# Board.net
KiCad netlist of a schematic drawn in Altium Designer
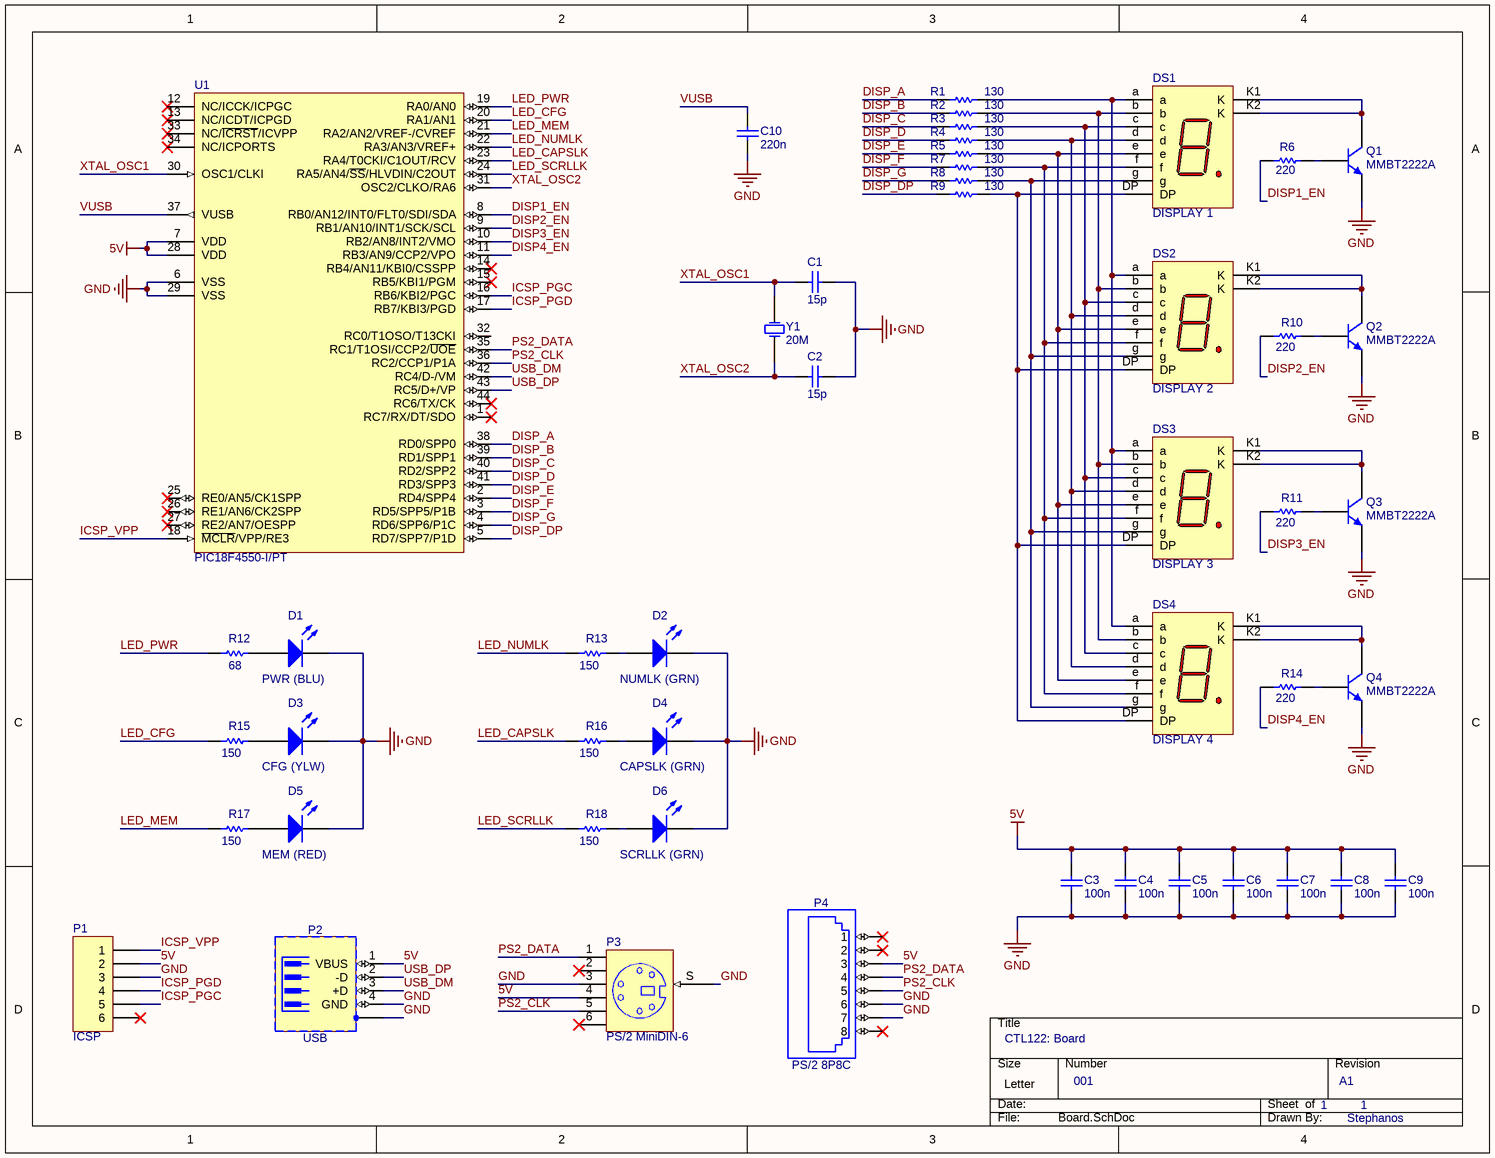
[diagram p0: Board.SchDoc]

(export (version "E")
  (design (tool "Eeschema 10.0.6"))
  (components
    (comp (ref "C1")
      (value "15p")
      (footprint "0805")
      (description "Capacitor")
      (fields (field (name "Comment") "CAP"))
      (libsource (lib "XNSFundamental") (part "CAP"))
    )
    (comp (ref "C2")
      (value "15p")
      (footprint "0805")
      (description "Capacitor")
      (fields (field (name "Comment") "CAP"))
      (libsource (lib "XNSFundamental") (part "CAP"))
    )
    (comp (ref "C3")
      (value "100n")
      (footprint "0805")
      (description "Capacitor")
      (fields (field (name "Comment") "CAP"))
      (libsource (lib "XNSFundamental") (part "CAP"))
    )
    (comp (ref "C4")
      (value "100n")
      (footprint "0805")
      (description "Capacitor")
      (fields (field (name "Comment") "CAP"))
      (libsource (lib "XNSFundamental") (part "CAP"))
    )
    (comp (ref "C5")
      (value "100n")
      (footprint "0805")
      (description "Capacitor")
      (fields (field (name "Comment") "CAP"))
      (libsource (lib "XNSFundamental") (part "CAP"))
    )
    (comp (ref "C6")
      (value "100n")
      (footprint "0805")
      (description "Capacitor")
      (fields (field (name "Comment") "CAP"))
      (libsource (lib "XNSFundamental") (part "CAP"))
    )
    (comp (ref "C7")
      (value "100n")
      (footprint "0805")
      (description "Capacitor")
      (fields (field (name "Comment") "CAP"))
      (libsource (lib "XNSFundamental") (part "CAP"))
    )
    (comp (ref "C8")
      (value "100n")
      (footprint "0805")
      (description "Capacitor")
      (fields (field (name "Comment") "CAP"))
      (libsource (lib "XNSFundamental") (part "CAP"))
    )
    (comp (ref "C9")
      (value "100n")
      (footprint "0805")
      (description "Capacitor")
      (fields (field (name "Comment") "CAP"))
      (libsource (lib "XNSFundamental") (part "CAP"))
    )
    (comp (ref "C10")
      (value "220n")
      (footprint "0805")
      (description "Capacitor")
      (fields (field (name "Comment") "CAP"))
      (libsource (lib "XNSFundamental") (part "CAP"))
    )
    (comp (ref "D1")
      (value "PWR (BLU)")
      (footprint "1206P")
      (description "Light Emitting Diode")
      (libsource (lib "XNSSemiconductor") (part "LED"))
    )
    (comp (ref "D2")
      (value "NUMLK (GRN)")
      (footprint "1206P")
      (description "Light Emitting Diode")
      (libsource (lib "XNSSemiconductor") (part "LED"))
    )
    (comp (ref "D3")
      (value "CFG (YLW)")
      (footprint "1206P")
      (description "Light Emitting Diode")
      (libsource (lib "XNSSemiconductor") (part "LED"))
    )
    (comp (ref "D4")
      (value "CAPSLK (GRN)")
      (footprint "1206P")
      (description "Light Emitting Diode")
      (libsource (lib "XNSSemiconductor") (part "LED"))
    )
    (comp (ref "D5")
      (value "MEM (RED)")
      (footprint "1206P")
      (description "Light Emitting Diode")
      (libsource (lib "XNSSemiconductor") (part "LED"))
    )
    (comp (ref "D6")
      (value "SCRLLK (GRN)")
      (footprint "1206P")
      (description "Light Emitting Diode")
      (libsource (lib "XNSSemiconductor") (part "LED"))
    )
    (comp (ref "DS1")
      (value "DISPLAY 1")
      (footprint "7SEG")
      (description "7-segment Display Common Cathode")
      (libsource (lib "XNSModule") (part "7SEG-CC"))
    )
    (comp (ref "DS2")
      (value "DISPLAY 2")
      (footprint "7SEG")
      (description "7-segment Display Common Cathode")
      (libsource (lib "XNSModule") (part "7SEG-CC"))
    )
    (comp (ref "DS3")
      (value "DISPLAY 3")
      (footprint "7SEG")
      (description "7-segment Display Common Cathode")
      (libsource (lib "XNSModule") (part "7SEG-CC"))
    )
    (comp (ref "DS4")
      (value "DISPLAY 4")
      (footprint "7SEG")
      (description "7-segment Display Common Cathode")
      (libsource (lib "XNSModule") (part "7SEG-CC"))
    )
    (comp (ref "P1")
      (value "ICSP")
      (footprint "HDR1X6")
      (description "Header, 6-Pin")
      (fields (field (name "PUBLISHER") "Altium Limited"))
      (libsource (lib "Miscellaneous Connectors") (part "Header 6"))
    )
    (comp (ref "P2")
      (value "USB")
      (footprint "TYCO_292304-1")
      (description "4 Pin + 1 Shield USB Receptacle")
      (fields
        (field (name "PART NUMBER") "TYCO_292304-1")
        (field (name "MANUFACTURER") "TYCO ELECTRONICS")
        (field (name "AUTHOR") "CERN DEM JLC")
      )
      (libsource (lib "Connectors") (part "Connector USB 4 Pin + 1Shield"))
    )
    (comp (ref "P3")
      (value "PS/2 MiniDIN-6")
      (footprint "PS2-6PIN")
      (description "6 Pin Through Hole PS2 Socket (Kycon P/N)")
      (fields (field (name "PUBLISHER") "Altium Limited"))
      (libsource (lib "Miscellaneous Connectors") (part "PS2-6PIN"))
    )
    (comp (ref "P4")
      (value "PS/2 8P8C")
      (footprint "FCI_54602-908LF")
      (description "1 Port, 8 Positions, CAT3 RJ45 Horizontal Modular Jack")
      (fields
        (field (name "PART NUMBER") "FCI_54602-908LF")
        (field (name "MANUFACTURER") "FCI")
        (field (name "AUTHOR") "CERN DEM JLC")
      )
      (libsource (lib "Connectors") (part "FCI_54602-908LF"))
    )
    (comp (ref "Q1")
      (value "MMBT2222A")
      (footprint "SOT-23")
      (description "Bipolar NPN Transistor")
      (libsource (lib "XNSSemiconductor") (part "NPN"))
    )
    (comp (ref "Q2")
      (value "MMBT2222A")
      (footprint "SOT-23")
      (description "Bipolar NPN Transistor")
      (libsource (lib "XNSSemiconductor") (part "NPN"))
    )
    (comp (ref "Q3")
      (value "MMBT2222A")
      (footprint "SOT-23")
      (description "Bipolar NPN Transistor")
      (libsource (lib "XNSSemiconductor") (part "NPN"))
    )
    (comp (ref "Q4")
      (value "MMBT2222A")
      (footprint "SOT-23")
      (description "Bipolar NPN Transistor")
      (libsource (lib "XNSSemiconductor") (part "NPN"))
    )
    (comp (ref "R1")
      (value "130")
      (footprint "0805")
      (description "Resistor")
      (fields (field (name "Comment") "RES"))
      (libsource (lib "XNSFundamental") (part "RES"))
    )
    (comp (ref "R2")
      (value "130")
      (footprint "0805")
      (description "Resistor")
      (fields (field (name "Comment") "RES"))
      (libsource (lib "XNSFundamental") (part "RES"))
    )
    (comp (ref "R3")
      (value "130")
      (footprint "0805")
      (description "Resistor")
      (fields (field (name "Comment") "RES"))
      (libsource (lib "XNSFundamental") (part "RES"))
    )
    (comp (ref "R4")
      (value "130")
      (footprint "0805")
      (description "Resistor")
      (fields (field (name "Comment") "RES"))
      (libsource (lib "XNSFundamental") (part "RES"))
    )
    (comp (ref "R5")
      (value "130")
      (footprint "0805")
      (description "Resistor")
      (fields (field (name "Comment") "RES"))
      (libsource (lib "XNSFundamental") (part "RES"))
    )
    (comp (ref "R6")
      (value "220")
      (footprint "0805")
      (description "Resistor")
      (fields (field (name "Comment") "RES"))
      (libsource (lib "XNSFundamental") (part "RES"))
    )
    (comp (ref "R7")
      (value "130")
      (footprint "0805")
      (description "Resistor")
      (fields (field (name "Comment") "RES"))
      (libsource (lib "XNSFundamental") (part "RES"))
    )
    (comp (ref "R8")
      (value "130")
      (footprint "0805")
      (description "Resistor")
      (fields (field (name "Comment") "RES"))
      (libsource (lib "XNSFundamental") (part "RES"))
    )
    (comp (ref "R9")
      (value "130")
      (footprint "0805")
      (description "Resistor")
      (fields (field (name "Comment") "RES"))
      (libsource (lib "XNSFundamental") (part "RES"))
    )
    (comp (ref "R10")
      (value "220")
      (footprint "0805")
      (description "Resistor")
      (fields (field (name "Comment") "RES"))
      (libsource (lib "XNSFundamental") (part "RES"))
    )
    (comp (ref "R11")
      (value "220")
      (footprint "0805")
      (description "Resistor")
      (fields (field (name "Comment") "RES"))
      (libsource (lib "XNSFundamental") (part "RES"))
    )
    (comp (ref "R12")
      (value "68")
      (footprint "0805")
      (description "Resistor")
      (fields (field (name "Comment") "RES"))
      (libsource (lib "XNSFundamental") (part "RES"))
    )
    (comp (ref "R13")
      (value "150")
      (footprint "0805")
      (description "Resistor")
      (fields (field (name "Comment") "RES"))
      (libsource (lib "XNSFundamental") (part "RES"))
    )
    (comp (ref "R14")
      (value "220")
      (footprint "0805")
      (description "Resistor")
      (fields (field (name "Comment") "RES"))
      (libsource (lib "XNSFundamental") (part "RES"))
    )
    (comp (ref "R15")
      (value "150")
      (footprint "0805")
      (description "Resistor")
      (fields (field (name "Comment") "RES"))
      (libsource (lib "XNSFundamental") (part "RES"))
    )
    (comp (ref "R16")
      (value "150")
      (footprint "0805")
      (description "Resistor")
      (fields (field (name "Comment") "RES"))
      (libsource (lib "XNSFundamental") (part "RES"))
    )
    (comp (ref "R17")
      (value "150")
      (footprint "0805")
      (description "Resistor")
      (fields (field (name "Comment") "RES"))
      (libsource (lib "XNSFundamental") (part "RES"))
    )
    (comp (ref "R18")
      (value "150")
      (footprint "0805")
      (description "Resistor")
      (fields (field (name "Comment") "RES"))
      (libsource (lib "XNSFundamental") (part "RES"))
    )
    (comp (ref "U1")
      (value "PIC18F4550-I/PT")
      (footprint "TQFP-PT44_N")
      (fields (field (name "PUBLISHER") "Altium Limited"))
      (libsource (lib "Microchip Microcontroller 8-Bit PIC18") (part "PIC18F4550-I/PT"))
    )
    (comp (ref "Y1")
      (value "20M")
      (footprint "HC49")
      (description "Crystal Oscillator")
      (fields (field (name "Comment") "XTAL"))
      (libsource (lib "XNSFundamental") (part "XTAL"))
    )
  )
  (nets
    (net (code "1") (name "/DISP1_EN") (class "Default")
      (node (ref "R6") (pin "1") (pinfunction "1_1") (pintype "passive"))
      (node (ref "U1") (pin "8") (pinfunction "RB0/AN12/INT0/FLT0/SDI/SDA_8") (pintype "bidirectional"))
    )
    (net (code "2") (name "/DISP2_EN") (class "Default")
      (node (ref "R10") (pin "1") (pinfunction "1_1") (pintype "passive"))
      (node (ref "U1") (pin "9") (pinfunction "RB1/AN10/INT1/SCK/SCL_9") (pintype "bidirectional"))
    )
    (net (code "3") (name "/DISP3_EN") (class "Default")
      (node (ref "R11") (pin "1") (pinfunction "1_1") (pintype "passive"))
      (node (ref "U1") (pin "10") (pinfunction "RB2/AN8/INT2/VMO_10") (pintype "bidirectional"))
    )
    (net (code "4") (name "/DISP4_EN") (class "Default")
      (node (ref "R14") (pin "1") (pinfunction "1_1") (pintype "passive"))
      (node (ref "U1") (pin "11") (pinfunction "RB3/AN9/CCP2/VPO_11") (pintype "bidirectional"))
    )
    (net (code "5") (name "/DISP_A") (class "Default")
      (node (ref "R1") (pin "1") (pinfunction "1_1") (pintype "passive"))
      (node (ref "U1") (pin "38") (pinfunction "RD0/SPP0_38") (pintype "bidirectional"))
    )
    (net (code "6") (name "/DISP_B") (class "Default")
      (node (ref "R2") (pin "1") (pinfunction "1_1") (pintype "passive"))
      (node (ref "U1") (pin "39") (pinfunction "RD1/SPP1_39") (pintype "bidirectional"))
    )
    (net (code "7") (name "/DISP_C") (class "Default")
      (node (ref "R3") (pin "1") (pinfunction "1_1") (pintype "passive"))
      (node (ref "U1") (pin "40") (pinfunction "RD2/SPP2_40") (pintype "bidirectional"))
    )
    (net (code "8") (name "/DISP_D") (class "Default")
      (node (ref "R4") (pin "1") (pinfunction "1_1") (pintype "passive"))
      (node (ref "U1") (pin "41") (pinfunction "RD3/SPP3_41") (pintype "bidirectional"))
    )
    (net (code "9") (name "/DISP_DP") (class "Default")
      (node (ref "R9") (pin "1") (pinfunction "1_1") (pintype "passive"))
      (node (ref "U1") (pin "5") (pinfunction "RD7/SPP7/P1D_5") (pintype "bidirectional"))
    )
    (net (code "10") (name "/DISP_E") (class "Default")
      (node (ref "R5") (pin "1") (pinfunction "1_1") (pintype "passive"))
      (node (ref "U1") (pin "2") (pinfunction "RD4/SPP4_2") (pintype "bidirectional"))
    )
    (net (code "11") (name "/DISP_F") (class "Default")
      (node (ref "R7") (pin "1") (pinfunction "1_1") (pintype "passive"))
      (node (ref "U1") (pin "3") (pinfunction "RD5/SPP5/P1B_3") (pintype "bidirectional"))
    )
    (net (code "12") (name "/DISP_G") (class "Default")
      (node (ref "R8") (pin "1") (pinfunction "1_1") (pintype "passive"))
      (node (ref "U1") (pin "4") (pinfunction "RD6/SPP6/P1C_4") (pintype "bidirectional"))
    )
    (net (code "13") (name "/ICSP_PGC") (class "Default")
      (node (ref "P1") (pin "5") (pinfunction "5_5") (pintype "passive"))
      (node (ref "U1") (pin "16") (pinfunction "RB6/KBI2/PGC_16") (pintype "bidirectional"))
    )
    (net (code "14") (name "/ICSP_PGD") (class "Default")
      (node (ref "P1") (pin "4") (pinfunction "4_4") (pintype "passive"))
      (node (ref "U1") (pin "17") (pinfunction "RB7/KBI3/PGD_17") (pintype "bidirectional"))
    )
    (net (code "15") (name "/ICSP_VPP") (class "Default")
      (node (ref "P1") (pin "1") (pinfunction "1_1") (pintype "passive"))
      (node (ref "U1") (pin "18") (pinfunction "~{MCLR}/VPP/RE3_18") (pintype "input"))
    )
    (net (code "16") (name "/LED_CAPSLK") (class "Default")
      (node (ref "R16") (pin "1") (pinfunction "1_1") (pintype "passive"))
      (node (ref "U1") (pin "23") (pinfunction "RA4/T0CKI/C1OUT/RCV_23") (pintype "bidirectional"))
    )
    (net (code "17") (name "/LED_CFG") (class "Default")
      (node (ref "R15") (pin "1") (pinfunction "1_1") (pintype "passive"))
      (node (ref "U1") (pin "20") (pinfunction "RA1/AN1_20") (pintype "bidirectional"))
    )
    (net (code "18") (name "/LED_MEM") (class "Default")
      (node (ref "R17") (pin "1") (pinfunction "1_1") (pintype "passive"))
      (node (ref "U1") (pin "21") (pinfunction "RA2/AN2/VREF-/CVREF_21") (pintype "bidirectional"))
    )
    (net (code "19") (name "/LED_NUMLK") (class "Default")
      (node (ref "R13") (pin "1") (pinfunction "1_1") (pintype "passive"))
      (node (ref "U1") (pin "22") (pinfunction "RA3/AN3/VREF+_22") (pintype "bidirectional"))
    )
    (net (code "20") (name "/LED_PWR") (class "Default")
      (node (ref "R12") (pin "1") (pinfunction "1_1") (pintype "passive"))
      (node (ref "U1") (pin "19") (pinfunction "RA0/AN0_19") (pintype "bidirectional"))
    )
    (net (code "21") (name "/LED_SCRLLK") (class "Default")
      (node (ref "R18") (pin "1") (pinfunction "1_1") (pintype "passive"))
      (node (ref "U1") (pin "24") (pinfunction "RA5/AN4/~{SS}/HLVDIN/C2OUT_24") (pintype "bidirectional"))
    )
    (net (code "22") (name "/PS2_CLK") (class "Default")
      (node (ref "P3") (pin "5") (pinfunction "5_5") (pintype "passive"))
      (node (ref "P4") (pin "5") (pinfunction "5_5") (pintype "bidirectional"))
      (node (ref "U1") (pin "36") (pinfunction "RC2/CCP1/P1A_36") (pintype "bidirectional"))
    )
    (net (code "23") (name "/PS2_DATA") (class "Default")
      (node (ref "P3") (pin "1") (pinfunction "1_1") (pintype "passive"))
      (node (ref "P4") (pin "4") (pinfunction "4_4") (pintype "bidirectional"))
      (node (ref "U1") (pin "35") (pinfunction "RC1/T1OSI/CCP2/~{UOE}_35") (pintype "bidirectional"))
    )
    (net (code "24") (name "/USB_DM") (class "Default")
      (node (ref "P2") (pin "3") (pinfunction "+D_3") (pintype "bidirectional"))
      (node (ref "U1") (pin "42") (pinfunction "RC4/D-/VM_42") (pintype "bidirectional"))
    )
    (net (code "25") (name "/USB_DP") (class "Default")
      (node (ref "P2") (pin "2") (pinfunction "-D_2") (pintype "bidirectional"))
      (node (ref "U1") (pin "43") (pinfunction "RC5/D+/VP_43") (pintype "bidirectional"))
    )
    (net (code "26") (name "/VUSB") (class "Default")
      (node (ref "C10") (pin "2") (pinfunction "2_2") (pintype "passive"))
      (node (ref "U1") (pin "37") (pinfunction "VUSB_37") (pintype "output"))
    )
    (net (code "27") (name "/XTAL_OSC1") (class "Default")
      (node (ref "C1") (pin "1") (pinfunction "1_1") (pintype "passive"))
      (node (ref "U1") (pin "30") (pinfunction "OSC1/CLKI_30") (pintype "input"))
      (node (ref "Y1") (pin "2") (pinfunction "2_2") (pintype "passive"))
    )
    (net (code "28") (name "/XTAL_OSC2") (class "Default")
      (node (ref "C2") (pin "1") (pinfunction "1_1") (pintype "passive"))
      (node (ref "U1") (pin "31") (pinfunction "OSC2/CLKO/RA6_31") (pintype "bidirectional"))
      (node (ref "Y1") (pin "1") (pinfunction "1_1") (pintype "passive"))
    )
    (net (code "29") (name "5V") (class "Default")
      (node (ref "C3") (pin "2") (pinfunction "2_2") (pintype "passive"))
      (node (ref "C4") (pin "2") (pinfunction "2_2") (pintype "passive"))
      (node (ref "C5") (pin "2") (pinfunction "2_2") (pintype "passive"))
      (node (ref "C6") (pin "2") (pinfunction "2_2") (pintype "passive"))
      (node (ref "C7") (pin "2") (pinfunction "2_2") (pintype "passive"))
      (node (ref "C8") (pin "2") (pinfunction "2_2") (pintype "passive"))
      (node (ref "C9") (pin "2") (pinfunction "2_2") (pintype "passive"))
      (node (ref "P1") (pin "2") (pinfunction "2_2") (pintype "passive"))
      (node (ref "P2") (pin "1") (pinfunction "VBUS_1") (pintype "bidirectional"))
      (node (ref "P3") (pin "4") (pinfunction "4_4") (pintype "passive"))
      (node (ref "P4") (pin "3") (pinfunction "3_3") (pintype "bidirectional"))
      (node (ref "U1") (pin "28") (pinfunction "VDD_28") (pintype "power_in"))
      (node (ref "U1") (pin "7") (pinfunction "VDD_7") (pintype "power_in"))
    )
    (net (code "30") (name "GND") (class "Default")
      (node (ref "C1") (pin "2") (pinfunction "2_2") (pintype "passive"))
      (node (ref "C10") (pin "1") (pinfunction "1_1") (pintype "passive"))
      (node (ref "C2") (pin "2") (pinfunction "2_2") (pintype "passive"))
      (node (ref "C3") (pin "1") (pinfunction "1_1") (pintype "passive"))
      (node (ref "C4") (pin "1") (pinfunction "1_1") (pintype "passive"))
      (node (ref "C5") (pin "1") (pinfunction "1_1") (pintype "passive"))
      (node (ref "C6") (pin "1") (pinfunction "1_1") (pintype "passive"))
      (node (ref "C7") (pin "1") (pinfunction "1_1") (pintype "passive"))
      (node (ref "C8") (pin "1") (pinfunction "1_1") (pintype "passive"))
      (node (ref "C9") (pin "1") (pinfunction "1_1") (pintype "passive"))
      (node (ref "D1") (pin "K") (pinfunction "K_K") (pintype "passive"))
      (node (ref "D2") (pin "K") (pinfunction "K_K") (pintype "passive"))
      (node (ref "D3") (pin "K") (pinfunction "K_K") (pintype "passive"))
      (node (ref "D4") (pin "K") (pinfunction "K_K") (pintype "passive"))
      (node (ref "D5") (pin "K") (pinfunction "K_K") (pintype "passive"))
      (node (ref "D6") (pin "K") (pinfunction "K_K") (pintype "passive"))
      (node (ref "P1") (pin "3") (pinfunction "3_3") (pintype "passive"))
      (node (ref "P2") (pin "4") (pinfunction "GND_4") (pintype "bidirectional"))
      (node (ref "P2") (pin "5") (pinfunction "SH_5") (pintype "power_in"))
      (node (ref "P3") (pin "3") (pinfunction "3_3") (pintype "passive"))
      (node (ref "P3") (pin "S") (pinfunction "S_S") (pintype "input"))
      (node (ref "P4") (pin "6") (pinfunction "6_6") (pintype "bidirectional"))
      (node (ref "P4") (pin "7") (pinfunction "7_7") (pintype "bidirectional"))
      (node (ref "Q1") (pin "E") (pinfunction "E_E") (pintype "passive"))
      (node (ref "Q2") (pin "E") (pinfunction "E_E") (pintype "passive"))
      (node (ref "Q3") (pin "E") (pinfunction "E_E") (pintype "passive"))
      (node (ref "Q4") (pin "E") (pinfunction "E_E") (pintype "passive"))
      (node (ref "U1") (pin "29") (pinfunction "VSS_29") (pintype "power_in"))
      (node (ref "U1") (pin "6") (pinfunction "VSS_6") (pintype "power_in"))
    )
    (net (code "31") (name "Net-(D1-PadA)") (class "Default")
      (node (ref "D1") (pin "A") (pinfunction "A_A") (pintype "passive"))
      (node (ref "R12") (pin "2") (pinfunction "2_2") (pintype "passive"))
    )
    (net (code "32") (name "Net-(D2-PadA)") (class "Default")
      (node (ref "D2") (pin "A") (pinfunction "A_A") (pintype "passive"))
      (node (ref "R13") (pin "2") (pinfunction "2_2") (pintype "passive"))
    )
    (net (code "33") (name "Net-(D3-PadA)") (class "Default")
      (node (ref "D3") (pin "A") (pinfunction "A_A") (pintype "passive"))
      (node (ref "R15") (pin "2") (pinfunction "2_2") (pintype "passive"))
    )
    (net (code "34") (name "Net-(D4-PadA)") (class "Default")
      (node (ref "D4") (pin "A") (pinfunction "A_A") (pintype "passive"))
      (node (ref "R16") (pin "2") (pinfunction "2_2") (pintype "passive"))
    )
    (net (code "35") (name "Net-(D5-PadA)") (class "Default")
      (node (ref "D5") (pin "A") (pinfunction "A_A") (pintype "passive"))
      (node (ref "R17") (pin "2") (pinfunction "2_2") (pintype "passive"))
    )
    (net (code "36") (name "Net-(D6-PadA)") (class "Default")
      (node (ref "D6") (pin "A") (pinfunction "A_A") (pintype "passive"))
      (node (ref "R18") (pin "2") (pinfunction "2_2") (pintype "passive"))
    )
    (net (code "37") (name "Net-(DS1-K-PadK1)") (class "Default")
      (node (ref "DS1") (pin "K1") (pinfunction "K_K1") (pintype "passive"))
      (node (ref "DS1") (pin "K2") (pinfunction "K_K2") (pintype "passive"))
      (node (ref "Q1") (pin "C") (pinfunction "C_C") (pintype "passive"))
    )
    (net (code "38") (name "Net-(DS1-PadDP)") (class "Default")
      (node (ref "DS1") (pin "DP") (pinfunction "DP_DP") (pintype "passive"))
      (node (ref "DS2") (pin "DP") (pinfunction "DP_DP") (pintype "passive"))
      (node (ref "DS3") (pin "DP") (pinfunction "DP_DP") (pintype "passive"))
      (node (ref "DS4") (pin "DP") (pinfunction "DP_DP") (pintype "passive"))
      (node (ref "R9") (pin "2") (pinfunction "2_2") (pintype "passive"))
    )
    (net (code "39") (name "Net-(DS1-Pada)") (class "Default")
      (node (ref "DS1") (pin "a") (pinfunction "a_a") (pintype "passive"))
      (node (ref "DS2") (pin "a") (pinfunction "a_a") (pintype "passive"))
      (node (ref "DS3") (pin "a") (pinfunction "a_a") (pintype "passive"))
      (node (ref "DS4") (pin "a") (pinfunction "a_a") (pintype "passive"))
      (node (ref "R1") (pin "2") (pinfunction "2_2") (pintype "passive"))
    )
    (net (code "40") (name "Net-(DS1-Padb)") (class "Default")
      (node (ref "DS1") (pin "b") (pinfunction "b_b") (pintype "passive"))
      (node (ref "DS2") (pin "b") (pinfunction "b_b") (pintype "passive"))
      (node (ref "DS3") (pin "b") (pinfunction "b_b") (pintype "passive"))
      (node (ref "DS4") (pin "b") (pinfunction "b_b") (pintype "passive"))
      (node (ref "R2") (pin "2") (pinfunction "2_2") (pintype "passive"))
    )
    (net (code "41") (name "Net-(DS1-Padc)") (class "Default")
      (node (ref "DS1") (pin "c") (pinfunction "c_c") (pintype "passive"))
      (node (ref "DS2") (pin "c") (pinfunction "c_c") (pintype "passive"))
      (node (ref "DS3") (pin "c") (pinfunction "c_c") (pintype "passive"))
      (node (ref "DS4") (pin "c") (pinfunction "c_c") (pintype "passive"))
      (node (ref "R3") (pin "2") (pinfunction "2_2") (pintype "passive"))
    )
    (net (code "42") (name "Net-(DS1-Padd)") (class "Default")
      (node (ref "DS1") (pin "d") (pinfunction "d_d") (pintype "passive"))
      (node (ref "DS2") (pin "d") (pinfunction "d_d") (pintype "passive"))
      (node (ref "DS3") (pin "d") (pinfunction "d_d") (pintype "passive"))
      (node (ref "DS4") (pin "d") (pinfunction "d_d") (pintype "passive"))
      (node (ref "R4") (pin "2") (pinfunction "2_2") (pintype "passive"))
    )
    (net (code "43") (name "Net-(DS1-Pade)") (class "Default")
      (node (ref "DS1") (pin "e") (pinfunction "e_e") (pintype "passive"))
      (node (ref "DS2") (pin "e") (pinfunction "e_e") (pintype "passive"))
      (node (ref "DS3") (pin "e") (pinfunction "e_e") (pintype "passive"))
      (node (ref "DS4") (pin "e") (pinfunction "e_e") (pintype "passive"))
      (node (ref "R5") (pin "2") (pinfunction "2_2") (pintype "passive"))
    )
    (net (code "44") (name "Net-(DS1-Padf)") (class "Default")
      (node (ref "DS1") (pin "f") (pinfunction "f_f") (pintype "passive"))
      (node (ref "DS2") (pin "f") (pinfunction "f_f") (pintype "passive"))
      (node (ref "DS3") (pin "f") (pinfunction "f_f") (pintype "passive"))
      (node (ref "DS4") (pin "f") (pinfunction "f_f") (pintype "passive"))
      (node (ref "R7") (pin "2") (pinfunction "2_2") (pintype "passive"))
    )
    (net (code "45") (name "Net-(DS1-Padg)") (class "Default")
      (node (ref "DS1") (pin "g") (pinfunction "g_g") (pintype "passive"))
      (node (ref "DS2") (pin "g") (pinfunction "g_g") (pintype "passive"))
      (node (ref "DS3") (pin "g") (pinfunction "g_g") (pintype "passive"))
      (node (ref "DS4") (pin "g") (pinfunction "g_g") (pintype "passive"))
      (node (ref "R8") (pin "2") (pinfunction "2_2") (pintype "passive"))
    )
    (net (code "46") (name "Net-(DS2-K-PadK1)") (class "Default")
      (node (ref "DS2") (pin "K1") (pinfunction "K_K1") (pintype "passive"))
      (node (ref "DS2") (pin "K2") (pinfunction "K_K2") (pintype "passive"))
      (node (ref "Q2") (pin "C") (pinfunction "C_C") (pintype "passive"))
    )
    (net (code "47") (name "Net-(DS3-K-PadK1)") (class "Default")
      (node (ref "DS3") (pin "K1") (pinfunction "K_K1") (pintype "passive"))
      (node (ref "DS3") (pin "K2") (pinfunction "K_K2") (pintype "passive"))
      (node (ref "Q3") (pin "C") (pinfunction "C_C") (pintype "passive"))
    )
    (net (code "48") (name "Net-(DS4-K-PadK1)") (class "Default")
      (node (ref "DS4") (pin "K1") (pinfunction "K_K1") (pintype "passive"))
      (node (ref "DS4") (pin "K2") (pinfunction "K_K2") (pintype "passive"))
      (node (ref "Q4") (pin "C") (pinfunction "C_C") (pintype "passive"))
    )
    (net (code "49") (name "Net-(Q1-PadB)") (class "Default")
      (node (ref "Q1") (pin "B") (pinfunction "B_B") (pintype "passive"))
      (node (ref "R6") (pin "2") (pinfunction "2_2") (pintype "passive"))
    )
    (net (code "50") (name "Net-(Q2-PadB)") (class "Default")
      (node (ref "Q2") (pin "B") (pinfunction "B_B") (pintype "passive"))
      (node (ref "R10") (pin "2") (pinfunction "2_2") (pintype "passive"))
    )
    (net (code "51") (name "Net-(Q3-PadB)") (class "Default")
      (node (ref "Q3") (pin "B") (pinfunction "B_B") (pintype "passive"))
      (node (ref "R11") (pin "2") (pinfunction "2_2") (pintype "passive"))
    )
    (net (code "52") (name "Net-(Q4-PadB)") (class "Default")
      (node (ref "Q4") (pin "B") (pinfunction "B_B") (pintype "passive"))
      (node (ref "R14") (pin "2") (pinfunction "2_2") (pintype "passive"))
    )
    (net (code "53") (name "unconnected-(P1-Pad6)") (class "Default")
      (node (ref "P1") (pin "6") (pinfunction "6_6") (pintype "passive+no_connect"))
    )
    (net (code "54") (name "unconnected-(P3-Pad2)") (class "Default")
      (node (ref "P3") (pin "2") (pinfunction "2_2") (pintype "passive+no_connect"))
    )
    (net (code "55") (name "unconnected-(P3-Pad6)") (class "Default")
      (node (ref "P3") (pin "6") (pinfunction "6_6") (pintype "passive+no_connect"))
    )
    (net (code "56") (name "unconnected-(P4-Pad1)") (class "Default")
      (node (ref "P4") (pin "1") (pinfunction "1_1") (pintype "bidirectional+no_connect"))
    )
    (net (code "57") (name "unconnected-(P4-Pad2)") (class "Default")
      (node (ref "P4") (pin "2") (pinfunction "2_2") (pintype "bidirectional+no_connect"))
    )
    (net (code "58") (name "unconnected-(P4-Pad8)") (class "Default")
      (node (ref "P4") (pin "8") (pinfunction "8_8") (pintype "bidirectional+no_connect"))
    )
    (net (code "59") (name "unconnected-(U1-NC{slash}ICCK{slash}ICPGC-Pad12)") (class "Default")
      (node (ref "U1") (pin "12") (pinfunction "NC/ICCK/ICPGC_12") (pintype "passive+no_connect"))
    )
    (net (code "60") (name "unconnected-(U1-NC{slash}ICDT{slash}ICPGD-Pad13)") (class "Default")
      (node (ref "U1") (pin "13") (pinfunction "NC/ICDT/ICPGD_13") (pintype "passive+no_connect"))
    )
    (net (code "61") (name "unconnected-(U1-NC{slash}ICPORTS-Pad34)") (class "Default")
      (node (ref "U1") (pin "34") (pinfunction "NC/ICPORTS_34") (pintype "passive+no_connect"))
    )
    (net (code "62") (name "unconnected-(U1-NC{slash}~{ICRST}{slash}ICVPP-Pad33)") (class "Default")
      (node (ref "U1") (pin "33") (pinfunction "NC/~{ICRST}/ICVPP_33") (pintype "passive+no_connect"))
    )
    (net (code "63") (name "unconnected-(U1-RB4{slash}AN11{slash}KBI0{slash}CSSPP-Pad14)") (class "Default")
      (node (ref "U1") (pin "14") (pinfunction "RB4/AN11/KBI0/CSSPP_14") (pintype "bidirectional+no_connect"))
    )
    (net (code "64") (name "unconnected-(U1-RB5{slash}KBI1{slash}PGM-Pad15)") (class "Default")
      (node (ref "U1") (pin "15") (pinfunction "RB5/KBI1/PGM_15") (pintype "bidirectional+no_connect"))
    )
    (net (code "65") (name "unconnected-(U1-RC0{slash}T1OSO{slash}T13CKI-Pad32)") (class "Default")
      (node (ref "U1") (pin "32") (pinfunction "RC0/T1OSO/T13CKI_32") (pintype "bidirectional"))
    )
    (net (code "66") (name "unconnected-(U1-RC6{slash}TX{slash}CK-Pad44)") (class "Default")
      (node (ref "U1") (pin "44") (pinfunction "RC6/TX/CK_44") (pintype "bidirectional+no_connect"))
    )
    (net (code "67") (name "unconnected-(U1-RC7{slash}RX{slash}DT{slash}SDO-Pad1)") (class "Default")
      (node (ref "U1") (pin "1") (pinfunction "RC7/RX/DT/SDO_1") (pintype "bidirectional+no_connect"))
    )
    (net (code "68") (name "unconnected-(U1-RE0{slash}AN5{slash}CK1SPP-Pad25)") (class "Default")
      (node (ref "U1") (pin "25") (pinfunction "RE0/AN5/CK1SPP_25") (pintype "bidirectional+no_connect"))
    )
    (net (code "69") (name "unconnected-(U1-RE1{slash}AN6{slash}CK2SPP-Pad26)") (class "Default")
      (node (ref "U1") (pin "26") (pinfunction "RE1/AN6/CK2SPP_26") (pintype "bidirectional+no_connect"))
    )
    (net (code "70") (name "unconnected-(U1-RE2{slash}AN7{slash}OESPP-Pad27)") (class "Default")
      (node (ref "U1") (pin "27") (pinfunction "RE2/AN7/OESPP_27") (pintype "bidirectional+no_connect"))
    )
  )
)
